# tempsens_tsys01.net
KiCad netlist of a schematic drawn in EAGLE
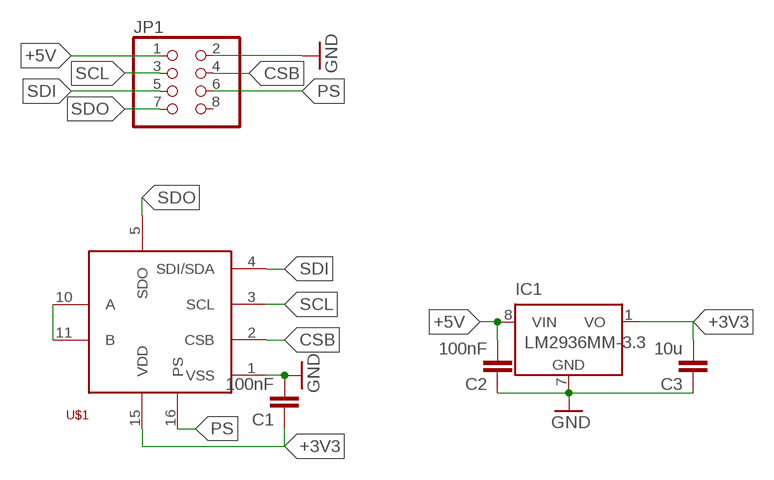
[diagram p0: schematic, sheet 1]

(export (version "E")
  (design (tool "Eeschema 10.0.6"))
  (components
    (comp (ref "C1")
      (value "100nF")
      (footprint "eagle-import:C0603K")
      (libsource (lib "eagle-import") (part "resistor_C-EUC0603K"))
    )
    (comp (ref "C2")
      (value "100nF")
      (footprint "eagle-import:C0603K")
      (libsource (lib "eagle-import") (part "resistor_C-EUC0603K"))
    )
    (comp (ref "C3")
      (value "10u")
      (footprint "eagle-import:C0805")
      (libsource (lib "eagle-import") (part "C-EUC0805"))
    )
    (comp (ref "IC1")
      (value "LM2936MM-3.3")
      (footprint "eagle-import:MINI-SO8")
      (fields (field (name "MF") "NATIONAL SEMICONDUCTOR") (field (name "MPN") "LM2936MM-3.3/NOPB"))
      (libsource (lib "eagle-import") (part "LM2936?MM-3.3"))
    )
    (comp (ref "JP1")
      (value "PINHD-2X4_2.00")
      (footprint "eagle-import:2X04M")
      (libsource (lib "eagle-import") (part "PINHD-2X4_2.00"))
    )
    (comp (ref "U$1")
      (value "TSYS01NOPAD")
      (footprint "eagle-import:TSYS01_NOPAD")
      (libsource (lib "eagle-import") (part "TSYS01NOPAD"))
    )
  )
  (nets
    (net (code "1") (name "+3V3") (class "Default")
      (node (ref "C1") (pin "1") (pinfunction "1_1") (pintype "passive"))
      (node (ref "C3") (pin "2") (pinfunction "2_2") (pintype "passive"))
      (node (ref "IC1") (pin "1") (pinfunction "VO_1") (pintype "passive"))
      (node (ref "U$1") (pin "15") (pinfunction "VDD_15") (pintype "bidirectional"))
    )
    (net (code "2") (name "+5V") (class "Default")
      (node (ref "C2") (pin "2") (pinfunction "2_2") (pintype "passive"))
      (node (ref "IC1") (pin "8") (pinfunction "VIN_8") (pintype "input"))
      (node (ref "JP1") (pin "1") (pinfunction "1_1") (pintype "passive"))
    )
    (net (code "3") (name "CSB") (class "Default")
      (node (ref "JP1") (pin "4") (pinfunction "4_4") (pintype "passive"))
      (node (ref "U$1") (pin "2") (pinfunction "CSB_2") (pintype "bidirectional"))
    )
    (net (code "4") (name "GND") (class "Default")
      (node (ref "C1") (pin "2") (pinfunction "2_2") (pintype "passive"))
      (node (ref "C2") (pin "1") (pinfunction "1_1") (pintype "passive"))
      (node (ref "C3") (pin "1") (pinfunction "1_1") (pintype "passive"))
      (node (ref "IC1") (pin "7") (pinfunction "GND_7") (pintype "passive"))
      (node (ref "JP1") (pin "2") (pinfunction "2_2") (pintype "passive"))
      (node (ref "U$1") (pin "1") (pinfunction "VSS_1") (pintype "bidirectional"))
    )
    (net (code "5") (name "Net-(U$1-A)") (class "Default")
      (node (ref "U$1") (pin "10") (pinfunction "A_10") (pintype "bidirectional"))
      (node (ref "U$1") (pin "11") (pinfunction "B_11") (pintype "bidirectional"))
    )
    (net (code "6") (name "PS") (class "Default")
      (node (ref "JP1") (pin "6") (pinfunction "6_6") (pintype "passive"))
      (node (ref "U$1") (pin "16") (pinfunction "PS_16") (pintype "bidirectional"))
    )
    (net (code "7") (name "SCL") (class "Default")
      (node (ref "JP1") (pin "3") (pinfunction "3_3") (pintype "passive"))
      (node (ref "U$1") (pin "3") (pinfunction "SCL_3") (pintype "bidirectional"))
    )
    (net (code "8") (name "SDI") (class "Default")
      (node (ref "JP1") (pin "5") (pinfunction "5_5") (pintype "passive"))
      (node (ref "U$1") (pin "4") (pinfunction "SDI/SDA_4") (pintype "bidirectional"))
    )
    (net (code "9") (name "SDO") (class "Default")
      (node (ref "JP1") (pin "7") (pinfunction "7_7") (pintype "passive"))
      (node (ref "U$1") (pin "5") (pinfunction "SDO_5") (pintype "bidirectional"))
    )
    (net (code "10") (name "unconnected-(JP1-Pad8)") (class "Default")
      (node (ref "JP1") (pin "8") (pinfunction "8_8") (pintype "passive"))
    )
  )
)
